# r8_3.net
KiCad netlist of a schematic drawn in EAGLE
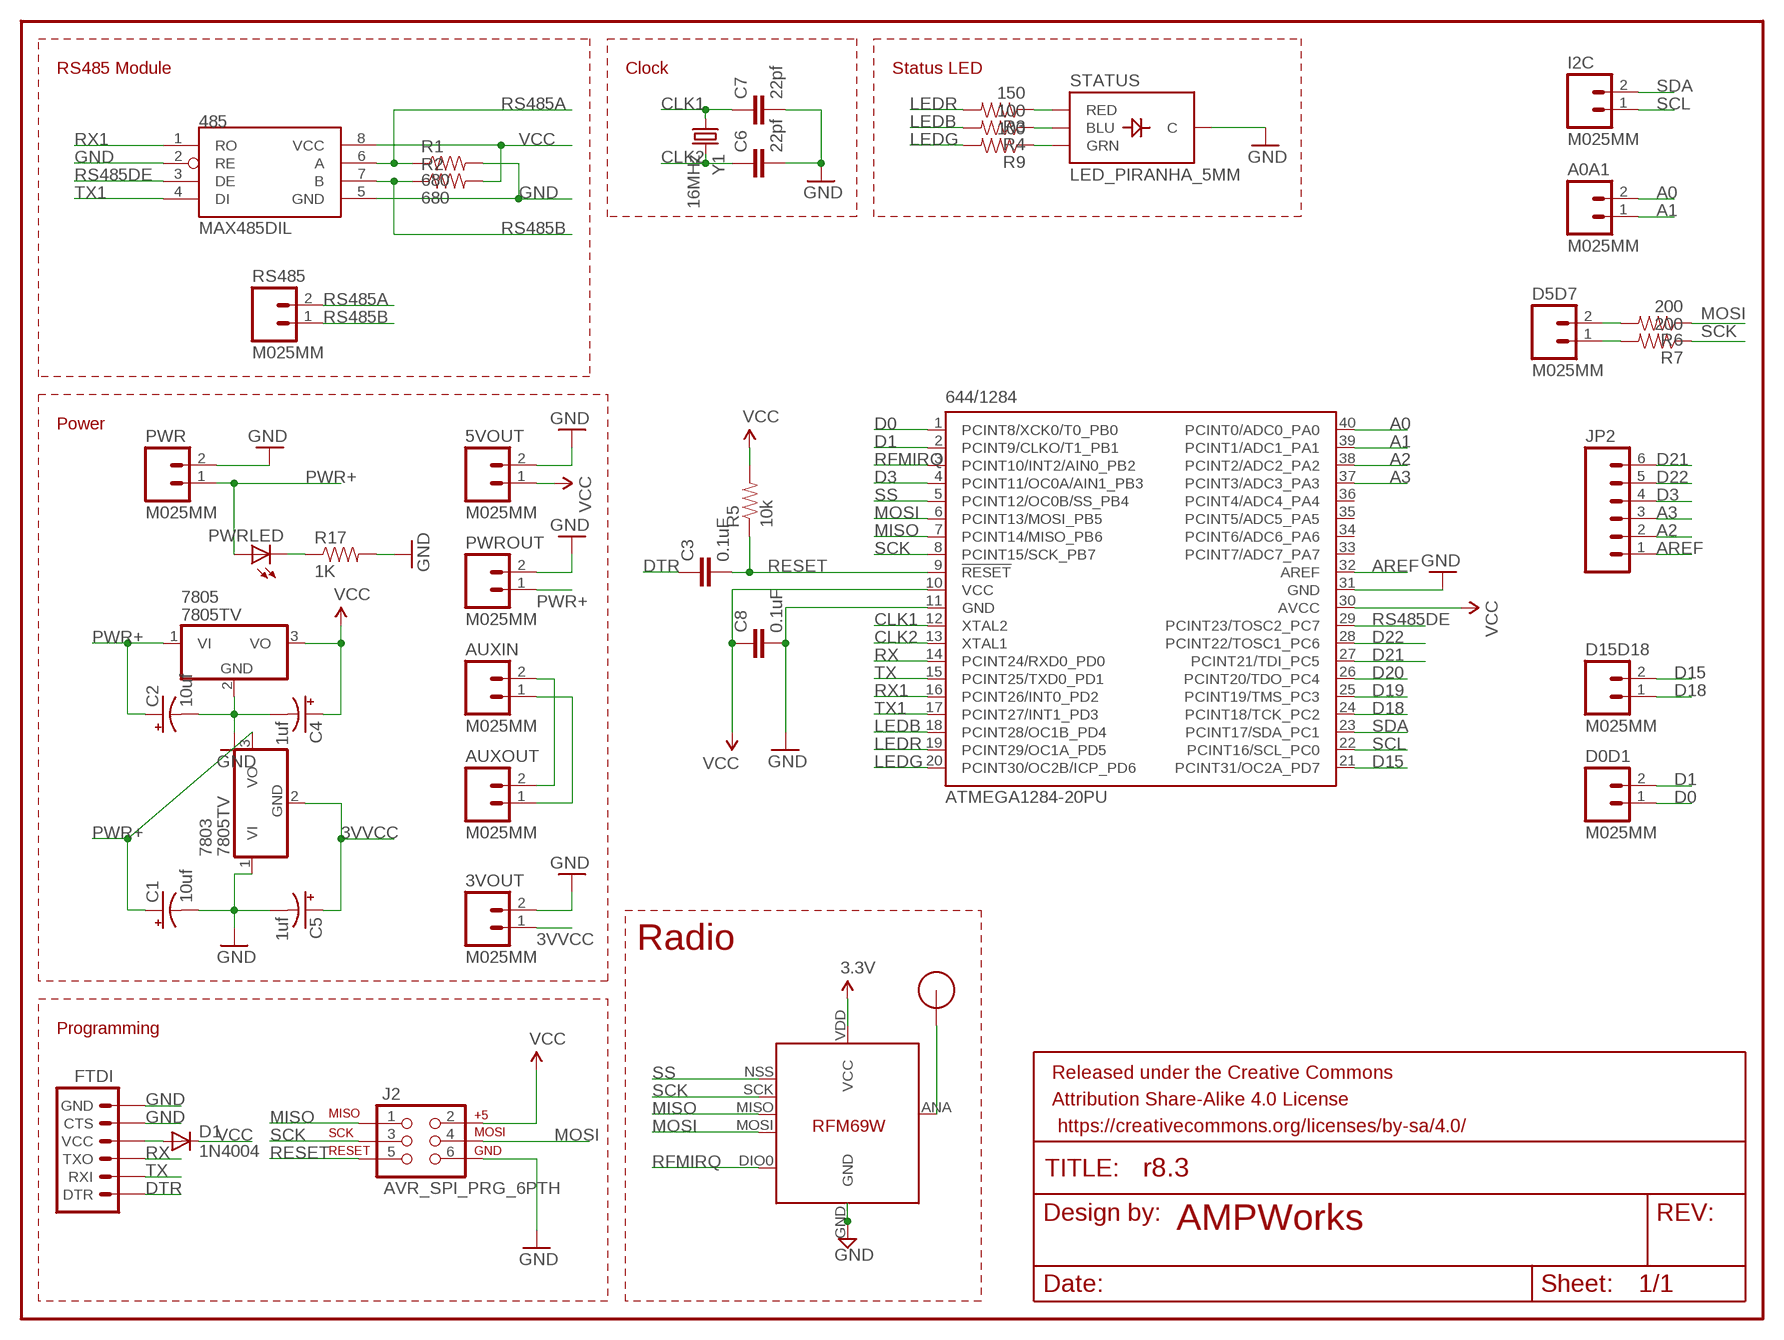
[diagram p0: schematic, sheet 1]

(export (version "E")
  (design (tool "Eeschema 10.0.6"))
  (components
    (comp (ref "3VOUT")
      (value "M025MM")
      (footprint "eagle-import:SCREWTERMINAL-5MM-2")
      (libsource (lib "eagle-import") (part "M025MM"))
    )
    (comp (ref "5VOUT")
      (value "M025MM")
      (footprint "eagle-import:SCREWTERMINAL-5MM-2")
      (libsource (lib "eagle-import") (part "M025MM"))
    )
    (comp (ref "485")
      (value "MAX485DIL")
      (footprint "eagle-import:DIL08")
      (libsource (lib "eagle-import") (part "MAX485DIL"))
    )
    (comp (ref "644/1284")
      (value "ATMEGA1284-20PU")
      (footprint "eagle-import:DIL40")
      (fields (field (name "MPN") "ATMEGA644-20PU"))
      (libsource (lib "eagle-import") (part "ATMEGA644-PU20"))
    )
    (comp (ref "7803")
      (value "7805TV")
      (footprint "eagle-import:TO220V")
      (libsource (lib "eagle-import") (part "78TV05"))
    )
    (comp (ref "7805")
      (value "7805TV")
      (footprint "eagle-import:TO220V")
      (libsource (lib "eagle-import") (part "78TV05"))
    )
    (comp (ref "A0A1")
      (value "M025MM")
      (footprint "eagle-import:SCREWTERMINAL-5MM-2")
      (libsource (lib "eagle-import") (part "M025MM"))
    )
    (comp (ref "AUXIN")
      (value "M025MM")
      (footprint "eagle-import:SCREWTERMINAL-5MM-2")
      (libsource (lib "eagle-import") (part "M025MM"))
    )
    (comp (ref "AUXOUT")
      (value "M025MM")
      (footprint "eagle-import:SCREWTERMINAL-5MM-2")
      (libsource (lib "eagle-import") (part "M025MM"))
    )
    (comp (ref "C1")
      (value "10uf")
      (footprint "eagle-import:CPOL-RADIAL-10UF-25V")
      (libsource (lib "eagle-import") (part "CAP_POLPTH2"))
    )
    (comp (ref "C2")
      (value "10uf")
      (footprint "eagle-import:CPOL-RADIAL-10UF-25V")
      (libsource (lib "eagle-import") (part "CAP_POLPTH2"))
    )
    (comp (ref "C3")
      (value "0.1uF")
      (footprint "eagle-import:CAP-PTH-SMALL")
      (libsource (lib "eagle-import") (part "CAPPTH"))
    )
    (comp (ref "C4")
      (value "1uf")
      (footprint "eagle-import:CPOL-RADIAL-10UF-25V")
      (libsource (lib "eagle-import") (part "CAP_POLPTH2"))
    )
    (comp (ref "C5")
      (value "1uf")
      (footprint "eagle-import:CPOL-RADIAL-10UF-25V")
      (libsource (lib "eagle-import") (part "CAP_POLPTH2"))
    )
    (comp (ref "C6")
      (value "22pf")
      (footprint "eagle-import:CAP-PTH-SMALL")
      (libsource (lib "eagle-import") (part "CAPPTH"))
    )
    (comp (ref "C7")
      (value "22pf")
      (footprint "eagle-import:CAP-PTH-SMALL")
      (libsource (lib "eagle-import") (part "CAPPTH"))
    )
    (comp (ref "C8")
      (value "0.1uF")
      (footprint "eagle-import:CAP-PTH-SMALL")
      (libsource (lib "eagle-import") (part "CAPPTH"))
    )
    (comp (ref "D0D1")
      (value "M025MM")
      (footprint "eagle-import:SCREWTERMINAL-5MM-2")
      (libsource (lib "eagle-import") (part "M025MM"))
    )
    (comp (ref "D1")
      (value "1N4004")
      (footprint "eagle-import:DO41-10")
      (libsource (lib "eagle-import") (part "1N4004"))
    )
    (comp (ref "D5D7")
      (value "M025MM")
      (footprint "eagle-import:SCREWTERMINAL-5MM-2")
      (libsource (lib "eagle-import") (part "M025MM"))
    )
    (comp (ref "D15D18")
      (value "M025MM")
      (footprint "eagle-import:SCREWTERMINAL-5MM-2")
      (libsource (lib "eagle-import") (part "M025MM"))
    )
    (comp (ref "FRAME1")
      (value "FRAME-LETTER")
      (footprint "eagle-import:CREATIVE_COMMONS")
      (libsource (lib "eagle-import") (part "FRAME-LETTER"))
    )
    (comp (ref "FTDI")
      (value "ARDUINO_SERIAL_PROGRAMPTH")
      (footprint "eagle-import:1X06")
      (libsource (lib "eagle-import") (part "ARDUINO_SERIAL_PROGRAMPTH"))
    )
    (comp (ref "I2C")
      (value "M025MM")
      (footprint "eagle-import:SCREWTERMINAL-5MM-2")
      (libsource (lib "eagle-import") (part "M025MM"))
    )
    (comp (ref "J2")
      (value "AVR_SPI_PRG_6PTH")
      (footprint "eagle-import:2X3")
      (libsource (lib "eagle-import") (part "AVR_SPI_PRG_6PTH"))
    )
    (comp (ref "JP2")
      (value "M06NO_SILK")
      (footprint "eagle-import:1X06_NO_SILK")
      (libsource (lib "eagle-import") (part "M06NO_SILK"))
    )
    (comp (ref "PWR")
      (value "M025MM")
      (footprint "eagle-import:SCREWTERMINAL-5MM-2")
      (libsource (lib "eagle-import") (part "M025MM"))
    )
    (comp (ref "PWRLED")
      (value "LED5MM")
      (footprint "eagle-import:LED5MM")
      (libsource (lib "eagle-import") (part "LED5MM"))
    )
    (comp (ref "PWROUT")
      (value "M025MM")
      (footprint "eagle-import:SCREWTERMINAL-5MM-2")
      (libsource (lib "eagle-import") (part "M025MM"))
    )
    (comp (ref "R1")
      (value "680")
      (footprint "eagle-import:AXIAL-0.4")
      (libsource (lib "eagle-import") (part "SparkFun-Resistors_RESISTORPTH-1/4W"))
    )
    (comp (ref "R2")
      (value "680")
      (footprint "eagle-import:AXIAL-0.4")
      (libsource (lib "eagle-import") (part "SparkFun-Resistors_RESISTORPTH-1/4W"))
    )
    (comp (ref "R3")
      (value "150")
      (footprint "eagle-import:AXIAL-0.4")
      (libsource (lib "eagle-import") (part "RESISTORPTH-1/4W"))
    )
    (comp (ref "R4")
      (value "100")
      (footprint "eagle-import:AXIAL-0.4")
      (libsource (lib "eagle-import") (part "RESISTORPTH-1/4W"))
    )
    (comp (ref "R5")
      (value "10k")
      (footprint "eagle-import:AXIAL-0.4")
      (libsource (lib "eagle-import") (part "RESISTORPTH-1/4W"))
    )
    (comp (ref "R6")
      (value "200")
      (footprint "eagle-import:AXIAL-0.4")
      (libsource (lib "eagle-import") (part "RESISTORPTH-1/4W"))
    )
    (comp (ref "R7")
      (value "200")
      (footprint "eagle-import:AXIAL-0.4")
      (libsource (lib "eagle-import") (part "RESISTORPTH-1/4W"))
    )
    (comp (ref "R9")
      (value "100")
      (footprint "eagle-import:AXIAL-0.4")
      (libsource (lib "eagle-import") (part "RESISTORPTH-1/4W"))
    )
    (comp (ref "R17")
      (value "1K")
      (footprint "eagle-import:AXIAL-0.4")
      (libsource (lib "eagle-import") (part "SparkFun-Resistors_RESISTORPTH-1/4W"))
    )
    (comp (ref "RMF69")
      (value "RFM69")
      (footprint "eagle-import:RFM69W-MINPADS")
      (libsource (lib "eagle-import") (part "RFM69"))
    )
    (comp (ref "RS485")
      (value "M025MM")
      (footprint "eagle-import:SCREWTERMINAL-5MM-2")
      (libsource (lib "eagle-import") (part "M025MM"))
    )
    (comp (ref "STATUS")
      (value "LED_PIRANHA_5MM")
      (footprint "eagle-import:LED_PIRANHA_5MM")
      (libsource (lib "eagle-import") (part "LED_PIRANHA_5MM"))
    )
    (comp (ref "U$1")
      (value "RFM12B_ANTENNA")
      (footprint "eagle-import:RFM12B-ANTENNA")
      (libsource (lib "eagle-import") (part "RFM12B_ANTENNA"))
    )
    (comp (ref "Y1")
      (value "16MHz")
      (footprint "eagle-import:HC49US")
      (libsource (lib "eagle-import") (part "CRYSTALHC49US"))
    )
  )
  (nets
    (net (code "1") (name "/A0") (class "Default")
      (node (ref "644/1284") (pin "40") (pinfunction "PCINT0/ADC0_PA0_40") (pintype "bidirectional"))
      (node (ref "A0A1") (pin "2") (pinfunction "2_2") (pintype "passive"))
    )
    (net (code "2") (name "/A1") (class "Default")
      (node (ref "644/1284") (pin "39") (pinfunction "PCINT1/ADC1_PA1_39") (pintype "bidirectional"))
      (node (ref "A0A1") (pin "1") (pinfunction "1_1") (pintype "passive"))
    )
    (net (code "3") (name "/A2") (class "Default")
      (node (ref "644/1284") (pin "38") (pinfunction "PCINT2/ADC2_PA2_38") (pintype "bidirectional"))
      (node (ref "JP2") (pin "2") (pinfunction "2_2") (pintype "passive"))
    )
    (net (code "4") (name "/A3") (class "Default")
      (node (ref "644/1284") (pin "37") (pinfunction "PCINT3/ADC3_PA3_37") (pintype "bidirectional"))
      (node (ref "JP2") (pin "3") (pinfunction "3_3") (pintype "passive"))
    )
    (net (code "5") (name "/AREF") (class "Default")
      (node (ref "644/1284") (pin "32") (pinfunction "AREF_32") (pintype "passive"))
      (node (ref "JP2") (pin "1") (pinfunction "1_1") (pintype "passive"))
    )
    (net (code "6") (name "/CLK1") (class "Default")
      (node (ref "644/1284") (pin "12") (pinfunction "XTAL2_12") (pintype "output"))
      (node (ref "C7") (pin "1") (pinfunction "1_1") (pintype "passive"))
      (node (ref "Y1") (pin "1") (pinfunction "1_1") (pintype "passive"))
    )
    (net (code "7") (name "/CLK2") (class "Default")
      (node (ref "644/1284") (pin "13") (pinfunction "XTAL1_13") (pintype "input"))
      (node (ref "C6") (pin "1") (pinfunction "1_1") (pintype "passive"))
      (node (ref "Y1") (pin "2") (pinfunction "2_2") (pintype "passive"))
    )
    (net (code "8") (name "/D0") (class "Default")
      (node (ref "644/1284") (pin "1") (pinfunction "PCINT8/XCK0/T0_PB0_1") (pintype "bidirectional"))
      (node (ref "D0D1") (pin "1") (pinfunction "1_1") (pintype "passive"))
    )
    (net (code "9") (name "/D1") (class "Default")
      (node (ref "644/1284") (pin "2") (pinfunction "PCINT9/CLKO/T1_PB1_2") (pintype "bidirectional"))
      (node (ref "D0D1") (pin "2") (pinfunction "2_2") (pintype "passive"))
    )
    (net (code "10") (name "/D3") (class "Default")
      (node (ref "644/1284") (pin "4") (pinfunction "PCINT11/OC0A/AIN1_PB3_4") (pintype "bidirectional"))
      (node (ref "JP2") (pin "4") (pinfunction "4_4") (pintype "passive"))
    )
    (net (code "11") (name "/D15") (class "Default")
      (node (ref "644/1284") (pin "21") (pinfunction "PCINT31/OC2A_PD7_21") (pintype "bidirectional"))
      (node (ref "D15D18") (pin "2") (pinfunction "2_2") (pintype "passive"))
    )
    (net (code "12") (name "/D18") (class "Default")
      (node (ref "644/1284") (pin "24") (pinfunction "PCINT18/TCK_PC2_24") (pintype "bidirectional"))
      (node (ref "D15D18") (pin "1") (pinfunction "1_1") (pintype "passive"))
    )
    (net (code "13") (name "/D19") (class "Default")
      (node (ref "644/1284") (pin "25") (pinfunction "PCINT19/TMS_PC3_25") (pintype "bidirectional"))
    )
    (net (code "14") (name "/D20") (class "Default")
      (node (ref "644/1284") (pin "26") (pinfunction "PCINT20/TDO_PC4_26") (pintype "bidirectional"))
    )
    (net (code "15") (name "/D21") (class "Default")
      (node (ref "644/1284") (pin "27") (pinfunction "PCINT21/TDI_PC5_27") (pintype "bidirectional"))
      (node (ref "JP2") (pin "6") (pinfunction "6_6") (pintype "passive"))
    )
    (net (code "16") (name "/D22") (class "Default")
      (node (ref "644/1284") (pin "28") (pinfunction "PCINT22/TOSC1_PC6_28") (pintype "bidirectional"))
      (node (ref "JP2") (pin "5") (pinfunction "5_5") (pintype "passive"))
    )
    (net (code "17") (name "/DTR") (class "Default")
      (node (ref "C3") (pin "1") (pinfunction "1_1") (pintype "passive"))
      (node (ref "FTDI") (pin "DTR") (pinfunction "DTR_DTR") (pintype "passive"))
    )
    (net (code "18") (name "/LEDB") (class "Default")
      (node (ref "644/1284") (pin "18") (pinfunction "PCINT28/OC1B_PD4_18") (pintype "bidirectional"))
      (node (ref "R4") (pin "P$2") (pinfunction "2_P$2") (pintype "passive"))
    )
    (net (code "19") (name "/LEDG") (class "Default")
      (node (ref "644/1284") (pin "20") (pinfunction "PCINT30/OC2B/ICP_PD6_20") (pintype "bidirectional"))
      (node (ref "R9") (pin "P$2") (pinfunction "2_P$2") (pintype "passive"))
    )
    (net (code "20") (name "/LEDR") (class "Default")
      (node (ref "644/1284") (pin "19") (pinfunction "PCINT29/OC1A_PD5_19") (pintype "bidirectional"))
      (node (ref "R3") (pin "P$2") (pinfunction "2_P$2") (pintype "passive"))
    )
    (net (code "21") (name "/MISO") (class "Default")
      (node (ref "644/1284") (pin "7") (pinfunction "PCINT14/MISO_PB6_7") (pintype "bidirectional"))
      (node (ref "J2") (pin "1") (pinfunction "1_1") (pintype "passive"))
      (node (ref "RMF69") (pin "MISO") (pinfunction "MISO_MISO") (pintype "input"))
    )
    (net (code "22") (name "/MOSI") (class "Default")
      (node (ref "644/1284") (pin "6") (pinfunction "PCINT13/MOSI_PB5_6") (pintype "bidirectional"))
      (node (ref "J2") (pin "4") (pinfunction "4_4") (pintype "passive"))
      (node (ref "R6") (pin "P$1") (pinfunction "1_P$1") (pintype "passive"))
      (node (ref "RMF69") (pin "MOSI") (pinfunction "MOSI_MOSI") (pintype "output"))
    )
    (net (code "23") (name "/PWR+") (class "Default")
      (node (ref "7803") (pin "3") (pinfunction "VO_3") (pintype "passive"))
      (node (ref "7805") (pin "1") (pinfunction "VI_1") (pintype "input"))
      (node (ref "C1") (pin "1") (pinfunction "+_1") (pintype "passive"))
      (node (ref "C2") (pin "1") (pinfunction "+_1") (pintype "passive"))
      (node (ref "PWR") (pin "1") (pinfunction "1_1") (pintype "passive"))
      (node (ref "PWRLED") (pin "A") (pinfunction "A_A") (pintype "passive"))
      (node (ref "PWROUT") (pin "1") (pinfunction "1_1") (pintype "passive"))
    )
    (net (code "24") (name "/RESET") (class "Default")
      (node (ref "644/1284") (pin "9") (pinfunction "~{RESET}_9") (pintype "input"))
      (node (ref "C3") (pin "2") (pinfunction "2_2") (pintype "passive"))
      (node (ref "J2") (pin "5") (pinfunction "5_5") (pintype "passive"))
      (node (ref "R5") (pin "P$1") (pinfunction "1_P$1") (pintype "passive"))
    )
    (net (code "25") (name "/RFMIRQ") (class "Default")
      (node (ref "644/1284") (pin "3") (pinfunction "PCINT10/INT2/AIN0_PB2_3") (pintype "bidirectional"))
      (node (ref "RMF69") (pin "DIO0") (pinfunction "DIO0_DIO0") (pintype "open_collector"))
    )
    (net (code "26") (name "/RS485A") (class "Default")
      (node (ref "485") (pin "6") (pinfunction "A_6") (pintype "bidirectional"))
      (node (ref "R1") (pin "P$1") (pinfunction "1_P$1") (pintype "passive"))
      (node (ref "RS485") (pin "2") (pinfunction "2_2") (pintype "passive"))
    )
    (net (code "27") (name "/RS485B") (class "Default")
      (node (ref "485") (pin "7") (pinfunction "B_7") (pintype "bidirectional"))
      (node (ref "R2") (pin "P$1") (pinfunction "1_P$1") (pintype "passive"))
      (node (ref "RS485") (pin "1") (pinfunction "1_1") (pintype "passive"))
    )
    (net (code "28") (name "/RS485DE") (class "Default")
      (node (ref "485") (pin "3") (pinfunction "DE_3") (pintype "bidirectional"))
      (node (ref "644/1284") (pin "29") (pinfunction "PCINT23/TOSC2_PC7_29") (pintype "bidirectional"))
    )
    (net (code "29") (name "/RX") (class "Default")
      (node (ref "644/1284") (pin "14") (pinfunction "PCINT24/RXD0_PD0_14") (pintype "bidirectional"))
      (node (ref "FTDI") (pin "TXO") (pinfunction "TXO_TXO") (pintype "passive"))
    )
    (net (code "30") (name "/RX1") (class "Default")
      (node (ref "485") (pin "1") (pinfunction "RO_1") (pintype "bidirectional"))
      (node (ref "644/1284") (pin "16") (pinfunction "PCINT26/INT0_PD2_16") (pintype "bidirectional"))
    )
    (net (code "31") (name "/SCK") (class "Default")
      (node (ref "644/1284") (pin "8") (pinfunction "PCINT15/SCK_PB7_8") (pintype "bidirectional"))
      (node (ref "J2") (pin "3") (pinfunction "3_3") (pintype "passive"))
      (node (ref "R7") (pin "P$1") (pinfunction "1_P$1") (pintype "passive"))
      (node (ref "RMF69") (pin "SCK") (pinfunction "SCK_SCK") (pintype "input"))
    )
    (net (code "32") (name "/SCL") (class "Default")
      (node (ref "644/1284") (pin "22") (pinfunction "PCINT16/SCL_PC0_22") (pintype "bidirectional"))
      (node (ref "I2C") (pin "1") (pinfunction "1_1") (pintype "passive"))
    )
    (net (code "33") (name "/SDA") (class "Default")
      (node (ref "644/1284") (pin "23") (pinfunction "PCINT17/SDA_PC1_23") (pintype "bidirectional"))
      (node (ref "I2C") (pin "2") (pinfunction "2_2") (pintype "passive"))
    )
    (net (code "34") (name "/SS") (class "Default")
      (node (ref "644/1284") (pin "5") (pinfunction "PCINT12/OC0B/SS_PB4_5") (pintype "bidirectional"))
      (node (ref "RMF69") (pin "NSS") (pinfunction "SEL_NSS") (pintype "input"))
    )
    (net (code "35") (name "/TX") (class "Default")
      (node (ref "644/1284") (pin "15") (pinfunction "PCINT25/TXD0_PD1_15") (pintype "bidirectional"))
      (node (ref "FTDI") (pin "RXI") (pinfunction "RXI_RXI") (pintype "passive"))
    )
    (net (code "36") (name "/TX1") (class "Default")
      (node (ref "485") (pin "4") (pinfunction "DI_4") (pintype "bidirectional"))
      (node (ref "644/1284") (pin "17") (pinfunction "PCINT27/INT1_PD3_17") (pintype "bidirectional"))
    )
    (net (code "37") (name "3.3V") (class "Default")
      (node (ref "3VOUT") (pin "1") (pinfunction "1_1") (pintype "passive"))
      (node (ref "7803") (pin "2") (pinfunction "GND_2") (pintype "passive"))
      (node (ref "C5") (pin "1") (pinfunction "+_1") (pintype "passive"))
      (node (ref "RMF69") (pin "VDD") (pinfunction "VCC_VDD") (pintype "power_in"))
    )
    (net (code "38") (name "GND") (class "Default")
      (node (ref "3VOUT") (pin "2") (pinfunction "2_2") (pintype "passive"))
      (node (ref "485") (pin "2") (pinfunction "RE_2") (pintype "bidirectional"))
      (node (ref "485") (pin "5") (pinfunction "GND_5") (pintype "bidirectional"))
      (node (ref "5VOUT") (pin "2") (pinfunction "2_2") (pintype "passive"))
      (node (ref "644/1284") (pin "11") (pinfunction "GND_11") (pintype "power_in"))
      (node (ref "644/1284") (pin "31") (pinfunction "GND_31") (pintype "power_in"))
      (node (ref "7803") (pin "1") (pinfunction "VI_1") (pintype "input"))
      (node (ref "7805") (pin "2") (pinfunction "GND_2") (pintype "passive"))
      (node (ref "C1") (pin "2") (pinfunction "-_2") (pintype "passive"))
      (node (ref "C2") (pin "2") (pinfunction "-_2") (pintype "passive"))
      (node (ref "C4") (pin "2") (pinfunction "-_2") (pintype "passive"))
      (node (ref "C5") (pin "2") (pinfunction "-_2") (pintype "passive"))
      (node (ref "C6") (pin "2") (pinfunction "2_2") (pintype "passive"))
      (node (ref "C7") (pin "2") (pinfunction "2_2") (pintype "passive"))
      (node (ref "C8") (pin "2") (pinfunction "2_2") (pintype "passive"))
      (node (ref "FTDI") (pin "CTS") (pinfunction "CTS_CTS") (pintype "passive"))
      (node (ref "FTDI") (pin "GND") (pinfunction "GND_GND") (pintype "passive"))
      (node (ref "J2") (pin "6") (pinfunction "6_6") (pintype "passive"))
      (node (ref "PWR") (pin "2") (pinfunction "2_2") (pintype "passive"))
      (node (ref "PWROUT") (pin "2") (pinfunction "2_2") (pintype "passive"))
      (node (ref "R1") (pin "P$2") (pinfunction "2_P$2") (pintype "passive"))
      (node (ref "R17") (pin "P$2") (pinfunction "2_P$2") (pintype "passive"))
      (node (ref "RMF69") (pin "GND") (pinfunction "GND_GND") (pintype "power_in"))
      (node (ref "STATUS") (pin "-") (pinfunction "C_-") (pintype "bidirectional"))
    )
    (net (code "39") (name "Net-(AUXIN-Pad1)") (class "Default")
      (node (ref "AUXIN") (pin "1") (pinfunction "1_1") (pintype "passive"))
      (node (ref "AUXOUT") (pin "1") (pinfunction "1_1") (pintype "passive"))
    )
    (net (code "40") (name "Net-(AUXIN-Pad2)") (class "Default")
      (node (ref "AUXIN") (pin "2") (pinfunction "2_2") (pintype "passive"))
      (node (ref "AUXOUT") (pin "2") (pinfunction "2_2") (pintype "passive"))
    )
    (net (code "41") (name "Net-(D1-PadA)") (class "Default")
      (node (ref "D1") (pin "A") (pinfunction "A_A") (pintype "passive"))
      (node (ref "FTDI") (pin "VCC") (pinfunction "VCC_VCC") (pintype "passive"))
    )
    (net (code "42") (name "Net-(PWRLED-C)") (class "Default")
      (node (ref "PWRLED") (pin "K") (pinfunction "C_K") (pintype "passive"))
      (node (ref "R17") (pin "P$1") (pinfunction "1_P$1") (pintype "passive"))
    )
    (net (code "43") (name "Net-(R3-1)") (class "Default")
      (node (ref "R3") (pin "P$1") (pinfunction "1_P$1") (pintype "passive"))
      (node (ref "STATUS") (pin "R") (pinfunction "RED_R") (pintype "bidirectional"))
    )
    (net (code "44") (name "Net-(R4-1)") (class "Default")
      (node (ref "R4") (pin "P$1") (pinfunction "1_P$1") (pintype "passive"))
      (node (ref "STATUS") (pin "B") (pinfunction "BLU_B") (pintype "bidirectional"))
    )
    (net (code "45") (name "Net-(R6-2)") (class "Default")
      (node (ref "D5D7") (pin "2") (pinfunction "2_2") (pintype "passive"))
      (node (ref "R6") (pin "P$2") (pinfunction "2_P$2") (pintype "passive"))
    )
    (net (code "46") (name "Net-(R7-2)") (class "Default")
      (node (ref "D5D7") (pin "1") (pinfunction "1_1") (pintype "passive"))
      (node (ref "R7") (pin "P$2") (pinfunction "2_P$2") (pintype "passive"))
    )
    (net (code "47") (name "Net-(R9-1)") (class "Default")
      (node (ref "R9") (pin "P$1") (pinfunction "1_P$1") (pintype "passive"))
      (node (ref "STATUS") (pin "G") (pinfunction "GRN_G") (pintype "bidirectional"))
    )
    (net (code "48") (name "Net-(RMF69-ANT)") (class "Default")
      (node (ref "RMF69") (pin "ANA") (pinfunction "ANT_ANA") (pintype "passive"))
      (node (ref "U$1") (pin "P$1") (pinfunction "1_P$1") (pintype "bidirectional"))
    )
    (net (code "49") (name "VCC") (class "Default")
      (node (ref "485") (pin "8") (pinfunction "VCC_8") (pintype "bidirectional"))
      (node (ref "5VOUT") (pin "1") (pinfunction "1_1") (pintype "passive"))
      (node (ref "644/1284") (pin "10") (pinfunction "VCC_10") (pintype "power_in"))
      (node (ref "644/1284") (pin "30") (pinfunction "AVCC_30") (pintype "power_in"))
      (node (ref "7805") (pin "3") (pinfunction "VO_3") (pintype "passive"))
      (node (ref "C4") (pin "1") (pinfunction "+_1") (pintype "passive"))
      (node (ref "C8") (pin "1") (pinfunction "1_1") (pintype "passive"))
      (node (ref "D1") (pin "C") (pinfunction "C_C") (pintype "passive"))
      (node (ref "J2") (pin "2") (pinfunction "2_2") (pintype "passive"))
      (node (ref "R2") (pin "P$2") (pinfunction "2_P$2") (pintype "passive"))
      (node (ref "R5") (pin "P$2") (pinfunction "2_P$2") (pintype "passive"))
    )
    (net (code "50") (name "unconnected-(644/1284-PCINT4{slash}ADC4_PA4-Pad36)") (class "Default")
      (node (ref "644/1284") (pin "36") (pinfunction "PCINT4/ADC4_PA4_36") (pintype "bidirectional"))
    )
    (net (code "51") (name "unconnected-(644/1284-PCINT5{slash}ADC5_PA5-Pad35)") (class "Default")
      (node (ref "644/1284") (pin "35") (pinfunction "PCINT5/ADC5_PA5_35") (pintype "bidirectional"))
    )
    (net (code "52") (name "unconnected-(644/1284-PCINT6{slash}ADC6_PA6-Pad34)") (class "Default")
      (node (ref "644/1284") (pin "34") (pinfunction "PCINT6/ADC6_PA6_34") (pintype "bidirectional"))
    )
    (net (code "53") (name "unconnected-(644/1284-PCINT7{slash}ADC7_PA7-Pad33)") (class "Default")
      (node (ref "644/1284") (pin "33") (pinfunction "PCINT7/ADC7_PA7_33") (pintype "bidirectional"))
    )
  )
)
